# arduino_pos_print_bilet_2020-11-19_14-39.net
KiCad netlist of a schematic drawn in EasyEDA
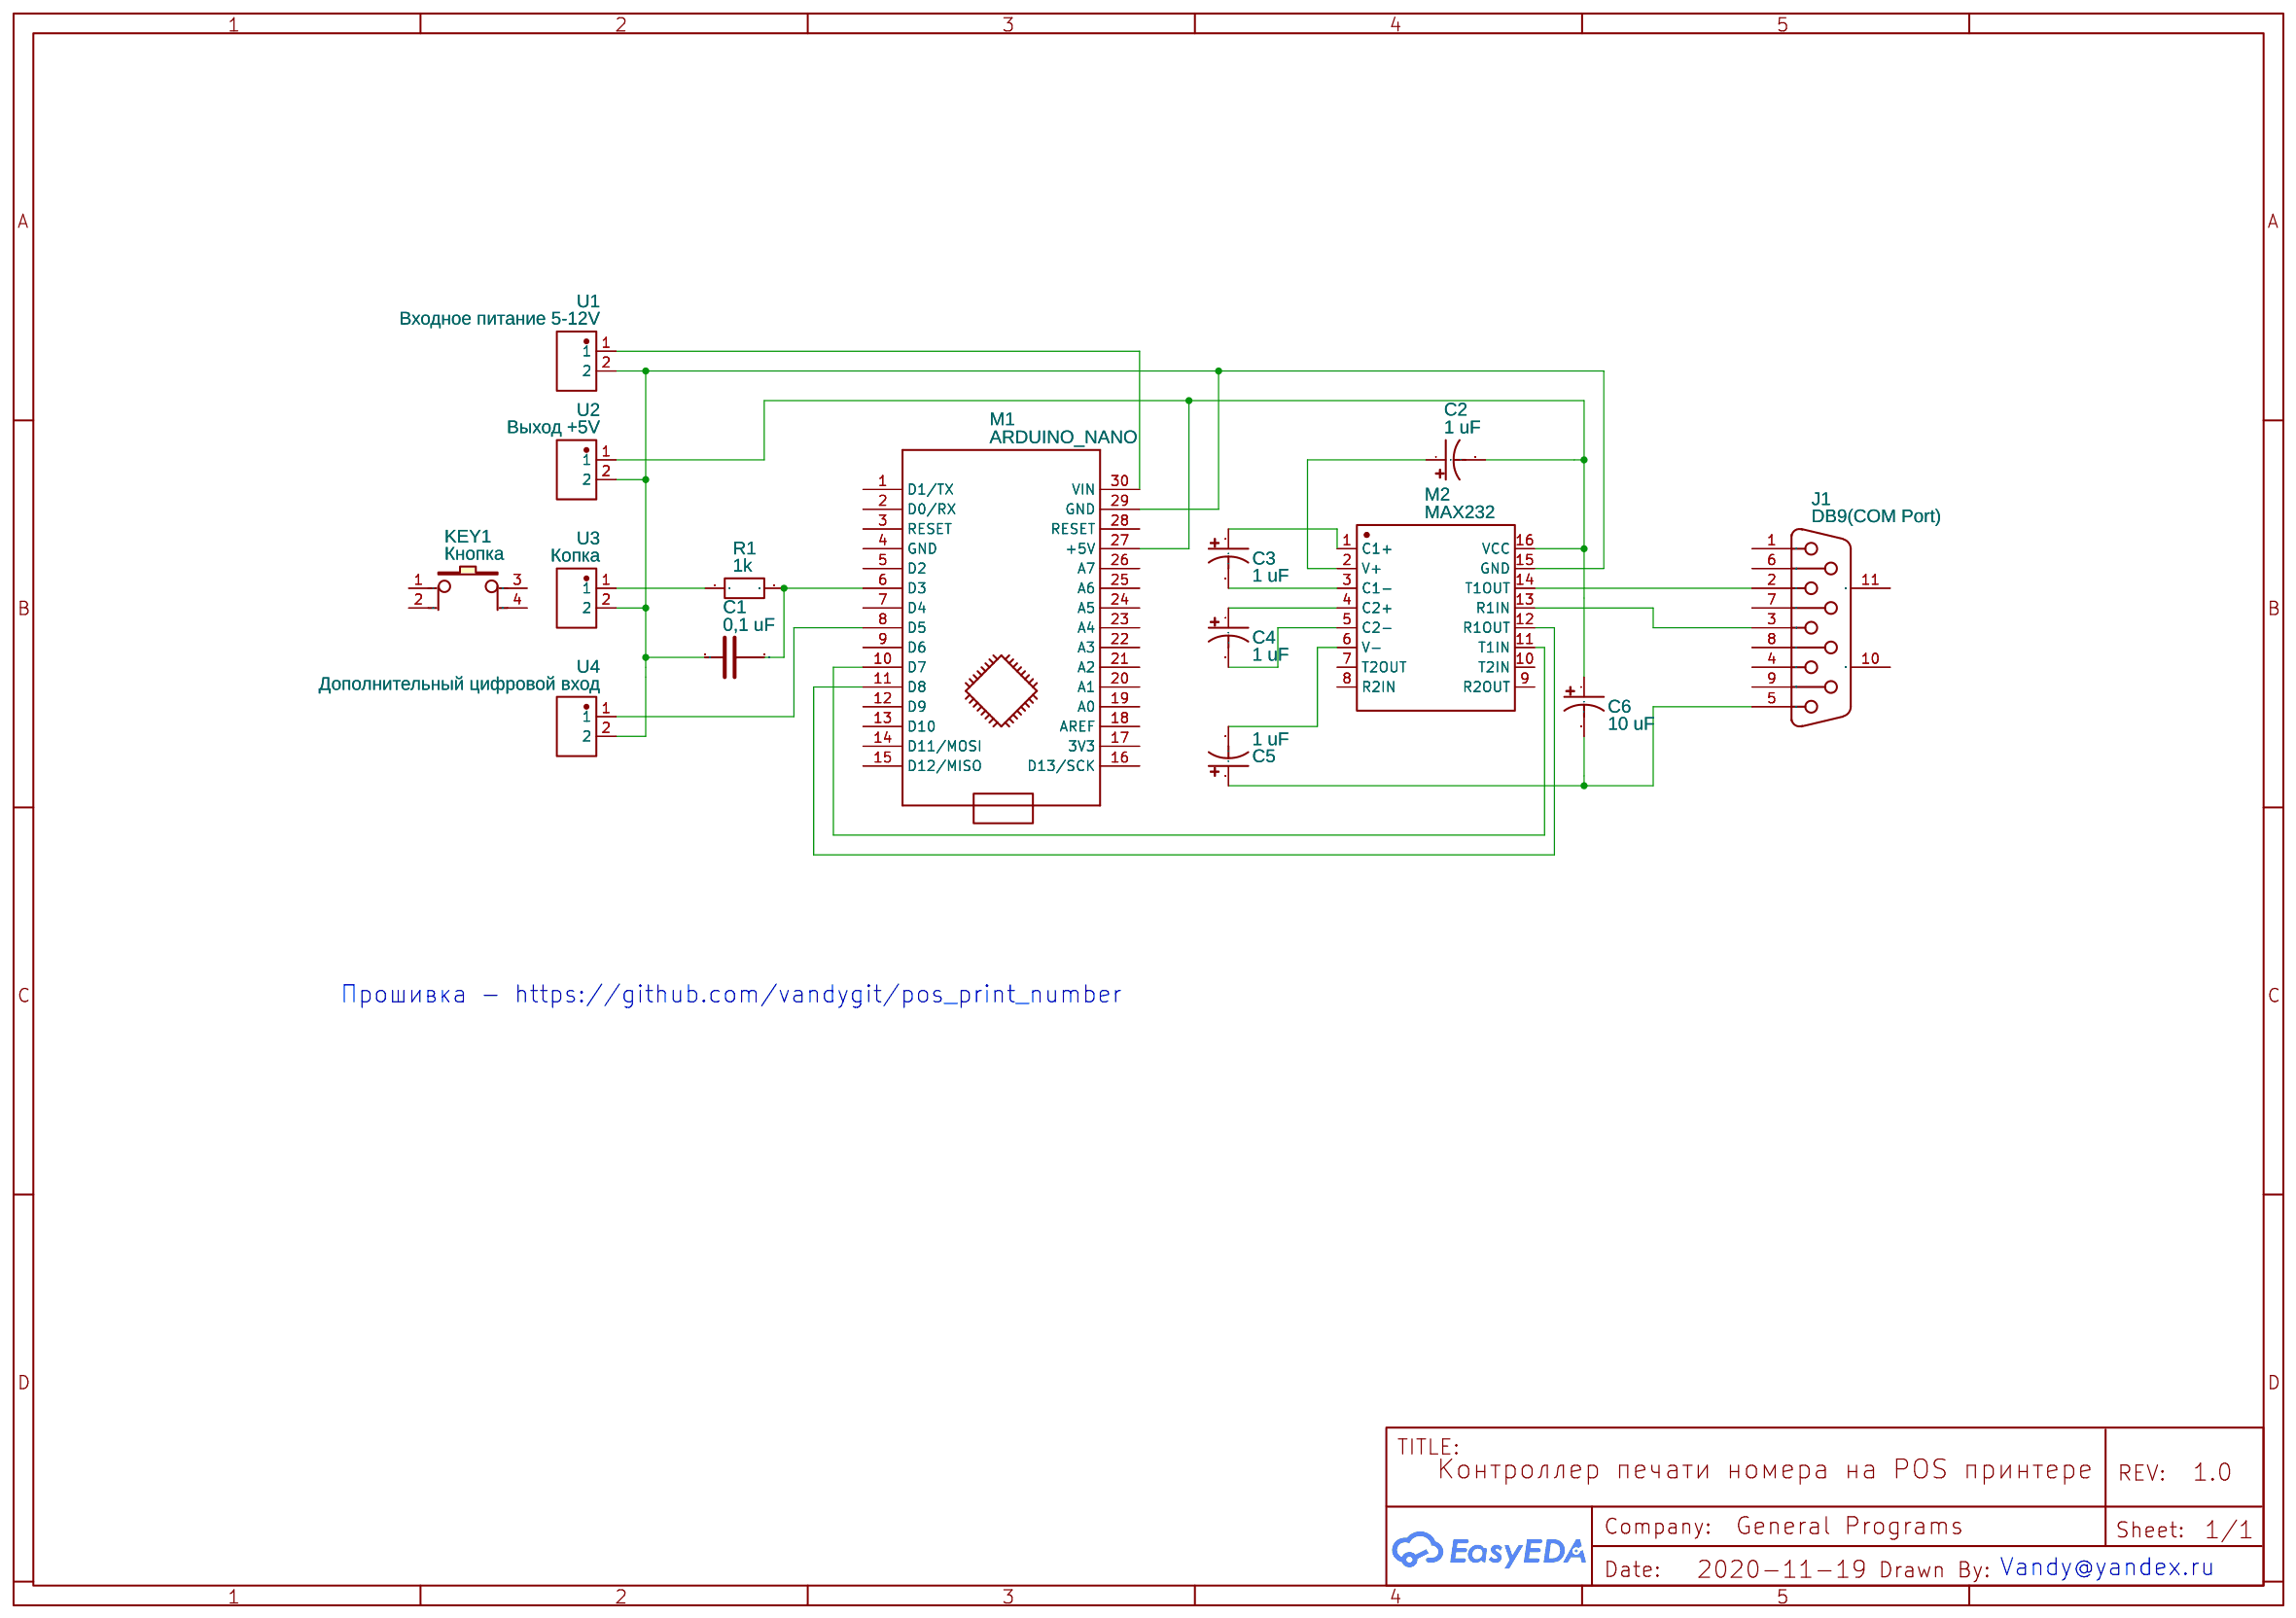
[diagram p0: schematic sheet]

(export (version "E")
  (design (tool "Eeschema 10.0.6"))
  (components
    (comp (ref "C1") (value "0,1 uF") (libsource (lib "") (part "CAPACITOR")))
    (comp (ref "C2") (value "1 uF") (libsource (lib "") (part "CAP_POLPTH2_1")))
    (comp (ref "C3") (value "1 uF") (libsource (lib "") (part "CAP_POLPTH2")))
    (comp (ref "C4") (value "1 uF") (libsource (lib "") (part "CAP_POLPTH2")))
    (comp (ref "C5") (value "1 uF") (libsource (lib "") (part "CAP_POLPTH2_2")))
    (comp (ref "C6") (value "10 uF") (libsource (lib "") (part "CAP_POLPTH2")))
    (comp (ref "J1")
      (value "DB9(COM Port)")
      (fields
        (field (name "BOM_Manufacturer Part") "DS1037-09MNAKT74-0CC")
        (field (name "BOM_Supplier Part") "C75750")
      )
      (libsource (lib "") (part "DS1037-09MNAKT74-0CC"))
    )
    (comp (ref "KEY1")
      (value "Кнопка")
      (fields
        (field (name "BOM_Manufacturer Part") "button6*6*8.5")
        (field (name "BOM_Supplier Part") "C59980")
      )
      (libsource (lib "") (part "button6*6*8.5"))
    )
    (comp (ref "M1") (value "ARDUINO_NANO") (libsource (lib "") (part "ARDUINO_NANO")))
    (comp (ref "M2") (value "MAX232") (libsource (lib "") (part "MAX232")))
    (comp (ref "R1")
      (value "1k")
      (fields
        (field (name "BOM_Manufacturer Part") "CFR0W4J0102A50")
        (field (name "BOM_Supplier Part") "C66649")
      )
      (libsource (lib "") (part "CFR0W4J0102A50_C66649"))
    )
    (comp (ref "U1")
      (value "Входное питание 5-12V")
      (fields
        (field (name "BOM_Manufacturer Part") "XY302V-3.5-2P")
        (field (name "BOM_Supplier Part") "C784940")
      )
      (libsource (lib "") (part "XY302V-3.5-2P"))
    )
    (comp (ref "U2")
      (value "Выход +5V")
      (fields
        (field (name "BOM_Manufacturer Part") "XY302V-3.5-2P")
        (field (name "BOM_Supplier Part") "C784940")
      )
      (libsource (lib "") (part "XY302V-3.5-2P"))
    )
    (comp (ref "U3")
      (value "Копка")
      (fields
        (field (name "BOM_Manufacturer Part") "XY302V-3.5-2P")
        (field (name "BOM_Supplier Part") "C784940")
      )
      (libsource (lib "") (part "XY302V-3.5-2P"))
    )
    (comp (ref "U4")
      (value "Дополнительный цифровой вход")
      (fields
        (field (name "BOM_Manufacturer Part") "XY302V-3.5-2P")
        (field (name "BOM_Supplier Part") "C784940")
      )
      (libsource (lib "") (part "XY302V-3.5-2P"))
    )
  )
  (nets
    (net (code "1") (name "Net-(C2-+)") (class "Default")
      (node (ref "C2") (pin "1") (pinfunction "+_1") (pintype "unspecified"))
      (node (ref "M2") (pin "2") (pinfunction "V+_2") (pintype "unspecified"))
    )
    (net (code "2") (name "Net-(C2--)") (class "Default")
      (node (ref "C2") (pin "2") (pinfunction "-_2") (pintype "unspecified"))
      (node (ref "C6") (pin "1") (pinfunction "+_1") (pintype "unspecified"))
      (node (ref "M1") (pin "27") (pinfunction "+5V_27") (pintype "unspecified"))
      (node (ref "M2") (pin "16") (pinfunction "VCC_16") (pintype "unspecified"))
      (node (ref "U2") (pin "1") (pinfunction "1_1") (pintype "unspecified"))
    )
    (net (code "3") (name "Net-(C3-+)") (class "Default")
      (node (ref "C3") (pin "1") (pinfunction "+_1") (pintype "unspecified"))
      (node (ref "M2") (pin "1") (pinfunction "C1+_1") (pintype "unspecified"))
    )
    (net (code "4") (name "Net-(C3--)") (class "Default")
      (node (ref "C3") (pin "2") (pinfunction "-_2") (pintype "unspecified"))
      (node (ref "M2") (pin "3") (pinfunction "C1-_3") (pintype "unspecified"))
    )
    (net (code "5") (name "Net-(C4-+)") (class "Default")
      (node (ref "C4") (pin "1") (pinfunction "+_1") (pintype "unspecified"))
      (node (ref "M2") (pin "4") (pinfunction "C2+_4") (pintype "unspecified"))
    )
    (net (code "6") (name "Net-(C4--)") (class "Default")
      (node (ref "C4") (pin "2") (pinfunction "-_2") (pintype "unspecified"))
      (node (ref "M2") (pin "5") (pinfunction "C2-_5") (pintype "unspecified"))
    )
    (net (code "7") (name "Net-(C5-+)") (class "Default")
      (node (ref "C5") (pin "1") (pinfunction "+_1") (pintype "unspecified"))
      (node (ref "C6") (pin "2") (pinfunction "-_2") (pintype "unspecified"))
      (node (ref "J1") (pin "5") (pinfunction "5_5") (pintype "input"))
    )
    (net (code "8") (name "Net-(C5--)") (class "Default")
      (node (ref "C5") (pin "2") (pinfunction "-_2") (pintype "unspecified"))
      (node (ref "M2") (pin "6") (pinfunction "V-_6") (pintype "unspecified"))
    )
    (net (code "9") (name "Net-(M1-D3)") (class "Default")
      (node (ref "C1") (pin "P$2") (pinfunction "P$2_P$2") (pintype "unspecified"))
      (node (ref "M1") (pin "6") (pinfunction "D3_6") (pintype "unspecified"))
      (node (ref "R1") (pin "2") (pinfunction "2_2") (pintype "unspecified"))
    )
    (net (code "10") (name "Net-(M1-D5)") (class "Default")
      (node (ref "M1") (pin "8") (pinfunction "D5_8") (pintype "unspecified"))
      (node (ref "U4") (pin "1") (pinfunction "1_1") (pintype "unspecified"))
    )
    (net (code "11") (name "Net-(M1-D7)") (class "Default")
      (node (ref "M1") (pin "10") (pinfunction "D7_10") (pintype "unspecified"))
      (node (ref "M2") (pin "11") (pinfunction "T1IN_11") (pintype "unspecified"))
    )
    (net (code "12") (name "Net-(M1-D8)") (class "Default")
      (node (ref "M1") (pin "11") (pinfunction "D8_11") (pintype "unspecified"))
      (node (ref "M2") (pin "12") (pinfunction "R1OUT_12") (pintype "unspecified"))
    )
    (net (code "13") (name "Net-(M1-VIN)") (class "Default")
      (node (ref "M1") (pin "30") (pinfunction "VIN_30") (pintype "unspecified"))
      (node (ref "U1") (pin "1") (pinfunction "1_1") (pintype "unspecified"))
    )
    (net (code "14") (name "Net-(M2-GND)") (class "Default")
      (node (ref "C1") (pin "P$1") (pinfunction "P$1_P$1") (pintype "unspecified"))
      (node (ref "M1") (pin "29") (pinfunction "GND_29") (pintype "unspecified"))
      (node (ref "M2") (pin "15") (pinfunction "GND_15") (pintype "unspecified"))
      (node (ref "U1") (pin "2") (pinfunction "2_2") (pintype "unspecified"))
      (node (ref "U2") (pin "2") (pinfunction "2_2") (pintype "unspecified"))
      (node (ref "U3") (pin "2") (pinfunction "2_2") (pintype "unspecified"))
      (node (ref "U4") (pin "2") (pinfunction "2_2") (pintype "unspecified"))
    )
    (net (code "15") (name "Net-(M2-R1IN)") (class "Default")
      (node (ref "J1") (pin "3") (pinfunction "3_3") (pintype "input"))
      (node (ref "M2") (pin "13") (pinfunction "R1IN_13") (pintype "unspecified"))
    )
    (net (code "16") (name "Net-(M2-T1OUT)") (class "Default")
      (node (ref "J1") (pin "2") (pinfunction "2_2") (pintype "input"))
      (node (ref "M2") (pin "14") (pinfunction "T1OUT_14") (pintype "unspecified"))
    )
    (net (code "17") (name "Net-(R1-Pad1)") (class "Default")
      (node (ref "R1") (pin "1") (pinfunction "1_1") (pintype "unspecified"))
      (node (ref "U3") (pin "1") (pinfunction "1_1") (pintype "unspecified"))
    )
    (net (code "18") (name "unconnected-(J1-MH1-Pad10)") (class "Default")
      (node (ref "J1") (pin "10") (pinfunction "MH1_10") (pintype "input"))
    )
    (net (code "19") (name "unconnected-(J1-MH2-Pad11)") (class "Default")
      (node (ref "J1") (pin "11") (pinfunction "MH2_11") (pintype "input"))
    )
    (net (code "20") (name "unconnected-(J1-Pad1)") (class "Default")
      (node (ref "J1") (pin "1") (pinfunction "1_1") (pintype "input"))
    )
    (net (code "21") (name "unconnected-(J1-Pad4)") (class "Default")
      (node (ref "J1") (pin "4") (pinfunction "4_4") (pintype "input"))
    )
    (net (code "22") (name "unconnected-(J1-Pad6)") (class "Default")
      (node (ref "J1") (pin "6") (pinfunction "6_6") (pintype "input"))
    )
    (net (code "23") (name "unconnected-(J1-Pad7)") (class "Default")
      (node (ref "J1") (pin "7") (pinfunction "7_7") (pintype "input"))
    )
    (net (code "24") (name "unconnected-(J1-Pad8)") (class "Default")
      (node (ref "J1") (pin "8") (pinfunction "8_8") (pintype "input"))
    )
    (net (code "25") (name "unconnected-(J1-Pad9)") (class "Default")
      (node (ref "J1") (pin "9") (pinfunction "9_9") (pintype "input"))
    )
    (net (code "26") (name "unconnected-(KEY1-Pad1)") (class "Default")
      (node (ref "KEY1") (pin "1") (pinfunction "1_1") (pintype "input"))
    )
    (net (code "27") (name "unconnected-(KEY1-Pad2)") (class "Default")
      (node (ref "KEY1") (pin "2") (pinfunction "2_2") (pintype "input"))
    )
    (net (code "28") (name "unconnected-(KEY1-Pad3)") (class "Default")
      (node (ref "KEY1") (pin "3") (pinfunction "3_3") (pintype "input"))
    )
    (net (code "29") (name "unconnected-(KEY1-Pad4)") (class "Default")
      (node (ref "KEY1") (pin "4") (pinfunction "4_4") (pintype "input"))
    )
    (net (code "30") (name "unconnected-(M1-3V3-Pad17)") (class "Default")
      (node (ref "M1") (pin "17") (pinfunction "3V3_17") (pintype "unspecified"))
    )
    (net (code "31") (name "unconnected-(M1-A0-Pad19)") (class "Default")
      (node (ref "M1") (pin "19") (pinfunction "A0_19") (pintype "unspecified"))
    )
    (net (code "32") (name "unconnected-(M1-A1-Pad20)") (class "Default")
      (node (ref "M1") (pin "20") (pinfunction "A1_20") (pintype "unspecified"))
    )
    (net (code "33") (name "unconnected-(M1-A2-Pad21)") (class "Default")
      (node (ref "M1") (pin "21") (pinfunction "A2_21") (pintype "unspecified"))
    )
    (net (code "34") (name "unconnected-(M1-A3-Pad22)") (class "Default")
      (node (ref "M1") (pin "22") (pinfunction "A3_22") (pintype "unspecified"))
    )
    (net (code "35") (name "unconnected-(M1-A4-Pad23)") (class "Default")
      (node (ref "M1") (pin "23") (pinfunction "A4_23") (pintype "unspecified"))
    )
    (net (code "36") (name "unconnected-(M1-A5-Pad24)") (class "Default")
      (node (ref "M1") (pin "24") (pinfunction "A5_24") (pintype "unspecified"))
    )
    (net (code "37") (name "unconnected-(M1-A6-Pad25)") (class "Default")
      (node (ref "M1") (pin "25") (pinfunction "A6_25") (pintype "unspecified"))
    )
    (net (code "38") (name "unconnected-(M1-A7-Pad26)") (class "Default")
      (node (ref "M1") (pin "26") (pinfunction "A7_26") (pintype "unspecified"))
    )
    (net (code "39") (name "unconnected-(M1-AREF-Pad18)") (class "Default")
      (node (ref "M1") (pin "18") (pinfunction "AREF_18") (pintype "unspecified"))
    )
    (net (code "40") (name "unconnected-(M1-D0{slash}RX-Pad2)") (class "Default")
      (node (ref "M1") (pin "2") (pinfunction "D0/RX_2") (pintype "unspecified"))
    )
    (net (code "41") (name "unconnected-(M1-D1{slash}TX-Pad1)") (class "Default")
      (node (ref "M1") (pin "1") (pinfunction "D1/TX_1") (pintype "unspecified"))
    )
    (net (code "42") (name "unconnected-(M1-D2-Pad5)") (class "Default")
      (node (ref "M1") (pin "5") (pinfunction "D2_5") (pintype "unspecified"))
    )
    (net (code "43") (name "unconnected-(M1-D4-Pad7)") (class "Default")
      (node (ref "M1") (pin "7") (pinfunction "D4_7") (pintype "unspecified"))
    )
    (net (code "44") (name "unconnected-(M1-D6-Pad9)") (class "Default")
      (node (ref "M1") (pin "9") (pinfunction "D6_9") (pintype "unspecified"))
    )
    (net (code "45") (name "unconnected-(M1-D9-Pad12)") (class "Default")
      (node (ref "M1") (pin "12") (pinfunction "D9_12") (pintype "unspecified"))
    )
    (net (code "46") (name "unconnected-(M1-D10-Pad13)") (class "Default")
      (node (ref "M1") (pin "13") (pinfunction "D10_13") (pintype "unspecified"))
    )
    (net (code "47") (name "unconnected-(M1-D11{slash}MOSI-Pad14)") (class "Default")
      (node (ref "M1") (pin "14") (pinfunction "D11/MOSI_14") (pintype "unspecified"))
    )
    (net (code "48") (name "unconnected-(M1-D12{slash}MISO-Pad15)") (class "Default")
      (node (ref "M1") (pin "15") (pinfunction "D12/MISO_15") (pintype "unspecified"))
    )
    (net (code "49") (name "unconnected-(M1-D13{slash}SCK-Pad16)") (class "Default")
      (node (ref "M1") (pin "16") (pinfunction "D13/SCK_16") (pintype "unspecified"))
    )
    (net (code "50") (name "unconnected-(M1-GND-Pad4)") (class "Default")
      (node (ref "M1") (pin "4") (pinfunction "GND_4") (pintype "unspecified"))
    )
    (net (code "51") (name "unconnected-(M1-RESET-Pad3)") (class "Default")
      (node (ref "M1") (pin "3") (pinfunction "RESET_3") (pintype "unspecified"))
    )
    (net (code "52") (name "unconnected-(M1-RESET-Pad28)") (class "Default")
      (node (ref "M1") (pin "28") (pinfunction "RESET_28") (pintype "unspecified"))
    )
    (net (code "53") (name "unconnected-(M2-R2IN-Pad8)") (class "Default")
      (node (ref "M2") (pin "8") (pinfunction "R2IN_8") (pintype "unspecified"))
    )
    (net (code "54") (name "unconnected-(M2-R2OUT-Pad9)") (class "Default")
      (node (ref "M2") (pin "9") (pinfunction "R2OUT_9") (pintype "unspecified"))
    )
    (net (code "55") (name "unconnected-(M2-T2IN-Pad10)") (class "Default")
      (node (ref "M2") (pin "10") (pinfunction "T2IN_10") (pintype "unspecified"))
    )
    (net (code "56") (name "unconnected-(M2-T2OUT-Pad7)") (class "Default")
      (node (ref "M2") (pin "7") (pinfunction "T2OUT_7") (pintype "unspecified"))
    )
  )
)
